# Mic-Breakout_v13.net
KiCad netlist of a schematic drawn in EAGLE
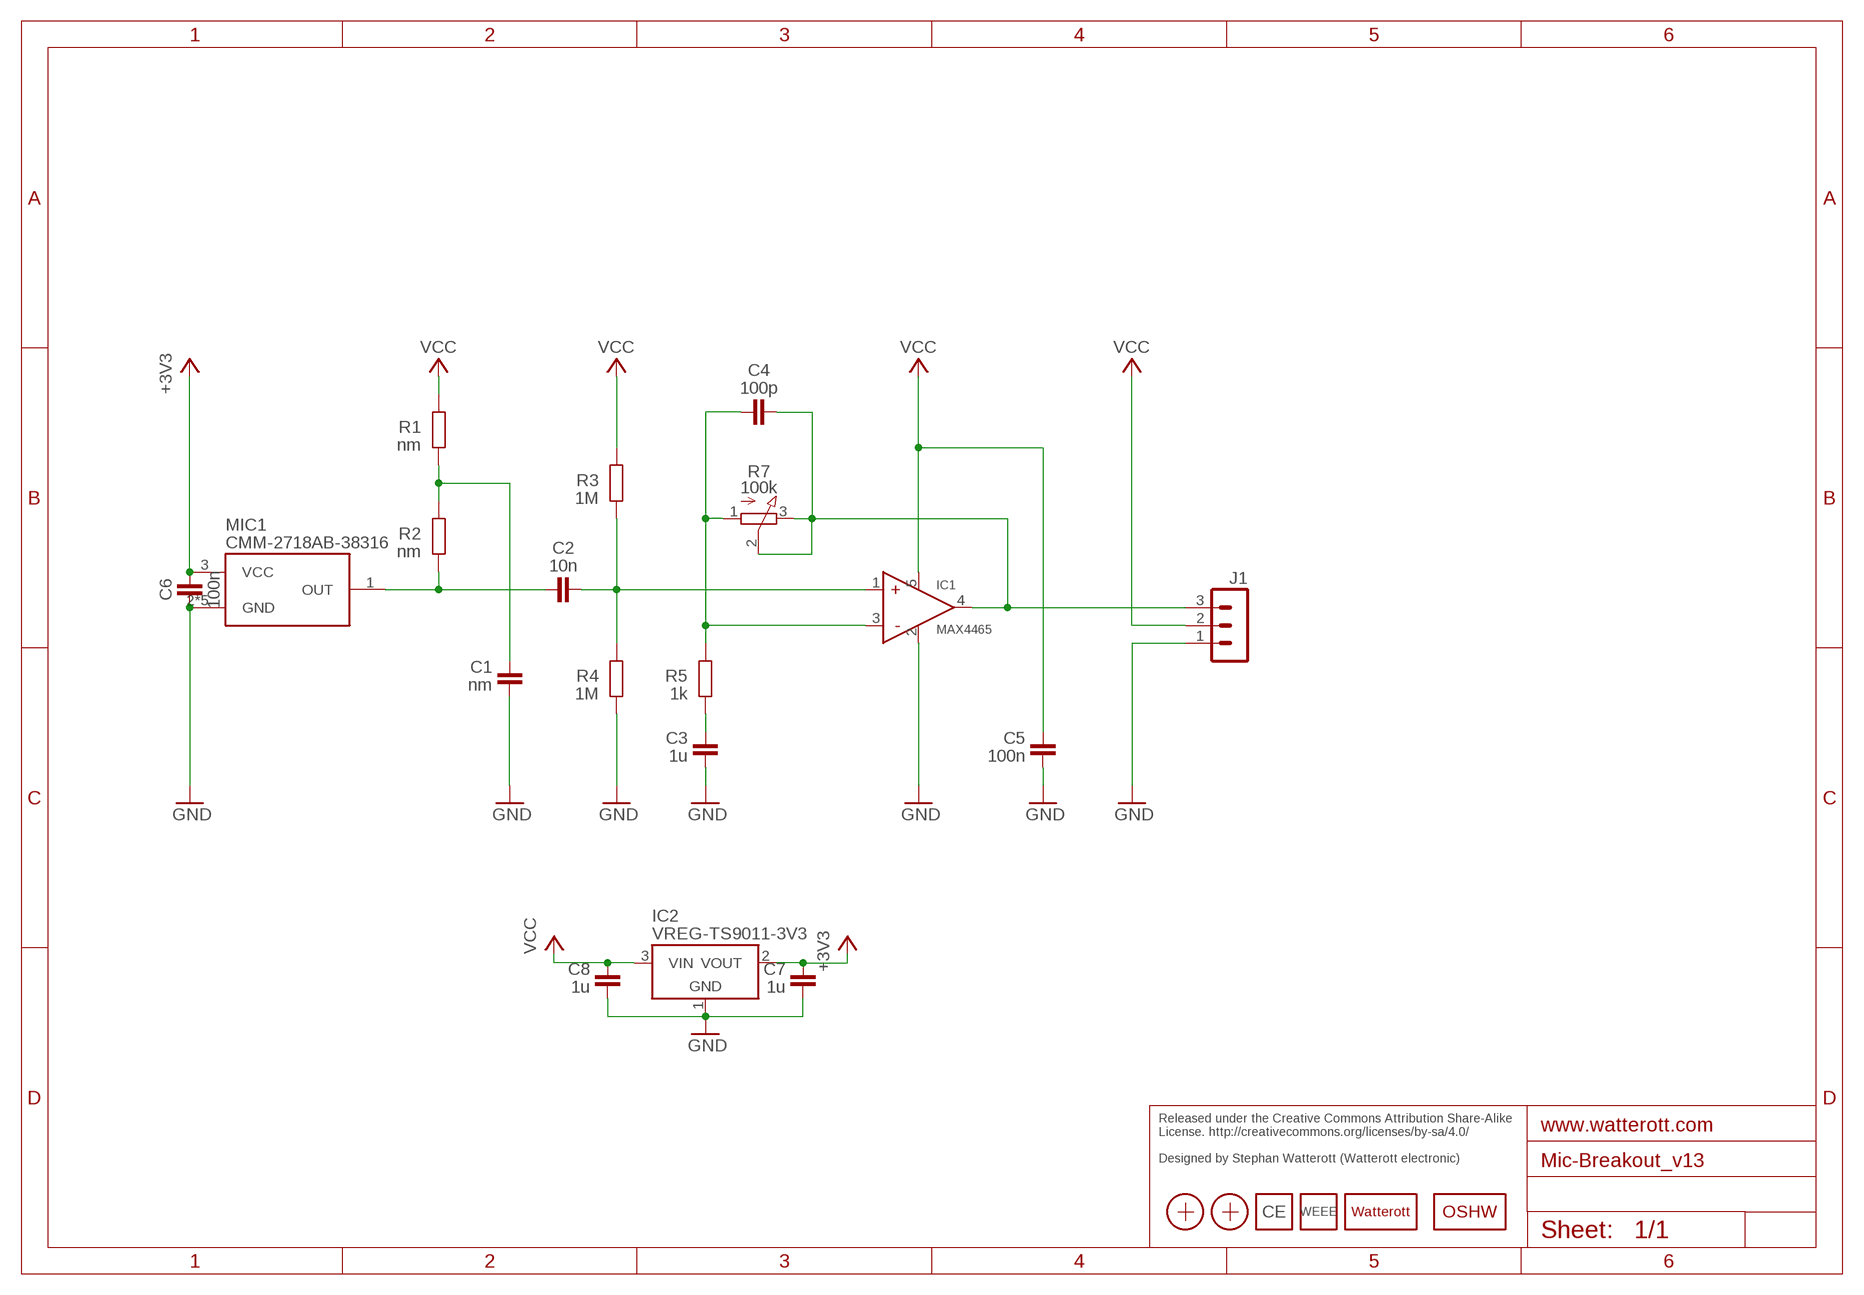
[diagram p0: schematic, sheet 1]

(export (version "E")
  (design (tool "Eeschema 10.0.6"))
  (components
    (comp (ref "C1")
      (value "nm")
      (footprint "eagle-import:C0402")
      (libsource (lib "eagle-import") (part "CAPACITOR-0402"))
    )
    (comp (ref "C2")
      (value "10n")
      (footprint "eagle-import:C0402")
      (libsource (lib "eagle-import") (part "CAPACITOR-0402"))
    )
    (comp (ref "C3")
      (value "1u")
      (footprint "eagle-import:C0402")
      (libsource (lib "eagle-import") (part "CAPACITOR-0402"))
    )
    (comp (ref "C4")
      (value "100p")
      (footprint "eagle-import:C0402")
      (libsource (lib "eagle-import") (part "CAPACITOR-0402"))
    )
    (comp (ref "C5")
      (value "100n")
      (footprint "eagle-import:C0402")
      (libsource (lib "eagle-import") (part "CAPACITOR-0402"))
    )
    (comp (ref "C6")
      (value "100n")
      (footprint "eagle-import:C0402")
      (libsource (lib "eagle-import") (part "CAPACITOR-0402"))
    )
    (comp (ref "C7")
      (value "1u")
      (footprint "eagle-import:C0402")
      (libsource (lib "eagle-import") (part "CAPACITOR-0402"))
    )
    (comp (ref "C8")
      (value "1u")
      (footprint "eagle-import:C0402")
      (libsource (lib "eagle-import") (part "CAPACITOR-0402"))
    )
    (comp (ref "IC1")
      (value "MAX4465")
      (footprint "eagle-import:SOT353")
      (libsource (lib "eagle-import") (part "MAX4465"))
    )
    (comp (ref "IC2")
      (value "VREG-TS9011-3V3")
      (footprint "eagle-import:SOT23")
      (libsource (lib "eagle-import") (part "VREG-TS9011-3V3"))
    )
    (comp (ref "J1")
      (value "MA03-1")
      (footprint "eagle-import:MA03-1")
      (libsource (lib "eagle-import") (part "MA03-1"))
    )
    (comp (ref "LOGO1")
      (value "LOGO-S_PLACE_M")
      (footprint "eagle-import:SPARK_TPLACE_M")
      (libsource (lib "eagle-import") (part "LOGO-S_PLACE_M"))
    )
    (comp (ref "LOGO2")
      (value "OSHW_LOGOX0100")
      (footprint "eagle-import:OSHW_6X100")
      (libsource (lib "eagle-import") (part "OSHW_LOGOX0100"))
    )
    (comp (ref "LOGO3")
      (value "LOGO_WEEE-4")
      (footprint "eagle-import:WEEE_4MM")
      (libsource (lib "eagle-import") (part "LOGO_WEEE-4"))
    )
    (comp (ref "LOGO4")
      (value "LOGO_CE-2")
      (footprint "eagle-import:CE_2MM")
      (libsource (lib "eagle-import") (part "LOGO_CE-2"))
    )
    (comp (ref "MIC1")
      (value "CMM-2718AB-38316")
      (footprint "eagle-import:CMM-2718AB-38316")
      (libsource (lib "eagle-import") (part "CMM-2718AB-38316CMM-2718AB-38316"))
    )
    (comp (ref "R1")
      (value "nm")
      (footprint "eagle-import:C0402")
      (libsource (lib "eagle-import") (part "RESISTOR-0402"))
    )
    (comp (ref "R2")
      (value "nm")
      (footprint "eagle-import:C0402")
      (libsource (lib "eagle-import") (part "RESISTOR-0402"))
    )
    (comp (ref "R3")
      (value "1M")
      (footprint "eagle-import:C0402")
      (libsource (lib "eagle-import") (part "RESISTOR-0402"))
    )
    (comp (ref "R4")
      (value "1M")
      (footprint "eagle-import:C0402")
      (libsource (lib "eagle-import") (part "RESISTOR-0402"))
    )
    (comp (ref "R5")
      (value "1k")
      (footprint "eagle-import:C0402")
      (libsource (lib "eagle-import") (part "RESISTOR-0402"))
    )
    (comp (ref "R7")
      (value "100k")
      (footprint "eagle-import:POT_EVM3Y")
      (libsource (lib "eagle-import") (part "POTEVM3Y"))
    )
    (comp (ref "X1")
      (value "PASSER-04")
      (footprint "eagle-import:PASSER_04MM")
      (libsource (lib "eagle-import") (part "PASSER-04"))
    )
    (comp (ref "X2")
      (value "PASSER-04")
      (footprint "eagle-import:PASSER_04MM")
      (libsource (lib "eagle-import") (part "PASSER-04"))
    )
  )
  (nets
    (net (code "1") (name "+3V3") (class "Default")
      (node (ref "C6") (pin "2") (pinfunction "2_2") (pintype "passive"))
      (node (ref "C7") (pin "2") (pinfunction "2_2") (pintype "passive"))
      (node (ref "IC2") (pin "2") (pinfunction "VOUT_2") (pintype "power_in"))
      (node (ref "MIC1") (pin "3") (pinfunction "VCC_3") (pintype "bidirectional"))
    )
    (net (code "2") (name "GND") (class "Default")
      (node (ref "C1") (pin "1") (pinfunction "1_1") (pintype "passive"))
      (node (ref "C3") (pin "1") (pinfunction "1_1") (pintype "passive"))
      (node (ref "C5") (pin "1") (pinfunction "1_1") (pintype "passive"))
      (node (ref "C6") (pin "1") (pinfunction "1_1") (pintype "passive"))
      (node (ref "C7") (pin "1") (pinfunction "1_1") (pintype "passive"))
      (node (ref "C8") (pin "1") (pinfunction "1_1") (pintype "passive"))
      (node (ref "IC1") (pin "2") (pinfunction "GND_2") (pintype "power_in"))
      (node (ref "IC2") (pin "1") (pinfunction "GND_1") (pintype "power_in"))
      (node (ref "J1") (pin "1") (pinfunction "1_1") (pintype "passive"))
      (node (ref "MIC1") (pin "2") (pinfunction "GND_2") (pintype "bidirectional"))
      (node (ref "MIC1") (pin "4") (pinfunction "GND_4") (pintype "bidirectional"))
      (node (ref "MIC1") (pin "5") (pinfunction "GND_5") (pintype "bidirectional"))
      (node (ref "MIC1") (pin "6") (pinfunction "GND_6") (pintype "bidirectional"))
      (node (ref "MIC1") (pin "7") (pinfunction "GND_7") (pintype "bidirectional"))
      (node (ref "R4") (pin "1") (pinfunction "1_1") (pintype "passive"))
    )
    (net (code "3") (name "Net-(C1-Pad2)") (class "Default")
      (node (ref "C1") (pin "2") (pinfunction "2_2") (pintype "passive"))
      (node (ref "R1") (pin "1") (pinfunction "1_1") (pintype "passive"))
      (node (ref "R2") (pin "2") (pinfunction "2_2") (pintype "passive"))
    )
    (net (code "4") (name "Net-(C3-Pad2)") (class "Default")
      (node (ref "C3") (pin "2") (pinfunction "2_2") (pintype "passive"))
      (node (ref "R5") (pin "1") (pinfunction "1_1") (pintype "passive"))
    )
    (net (code "5") (name "Net-(IC1-+)") (class "Default")
      (node (ref "C2") (pin "2") (pinfunction "2_2") (pintype "passive"))
      (node (ref "IC1") (pin "1") (pinfunction "+_1") (pintype "input"))
      (node (ref "R3") (pin "1") (pinfunction "1_1") (pintype "passive"))
      (node (ref "R4") (pin "2") (pinfunction "2_2") (pintype "passive"))
    )
    (net (code "6") (name "Net-(IC1--)") (class "Default")
      (node (ref "C4") (pin "2") (pinfunction "2_2") (pintype "passive"))
      (node (ref "IC1") (pin "3") (pinfunction "-_3") (pintype "input"))
      (node (ref "R5") (pin "2") (pinfunction "2_2") (pintype "passive"))
      (node (ref "R7") (pin "1") (pinfunction "A_1") (pintype "passive"))
    )
    (net (code "7") (name "Net-(IC1-OUT)") (class "Default")
      (node (ref "C4") (pin "1") (pinfunction "1_1") (pintype "passive"))
      (node (ref "IC1") (pin "4") (pinfunction "OUT_4") (pintype "output"))
      (node (ref "J1") (pin "3") (pinfunction "3_3") (pintype "passive"))
      (node (ref "R7") (pin "2") (pinfunction "S_2") (pintype "passive"))
      (node (ref "R7") (pin "3") (pinfunction "E_3") (pintype "passive"))
    )
    (net (code "8") (name "Net-(MIC1-OUT)") (class "Default")
      (node (ref "C2") (pin "1") (pinfunction "1_1") (pintype "passive"))
      (node (ref "MIC1") (pin "1") (pinfunction "OUT_1") (pintype "bidirectional"))
      (node (ref "R2") (pin "1") (pinfunction "1_1") (pintype "passive"))
    )
    (net (code "9") (name "VCC") (class "Default")
      (node (ref "C5") (pin "2") (pinfunction "2_2") (pintype "passive"))
      (node (ref "C8") (pin "2") (pinfunction "2_2") (pintype "passive"))
      (node (ref "IC1") (pin "5") (pinfunction "VCC_5") (pintype "power_in"))
      (node (ref "IC2") (pin "3") (pinfunction "VIN_3") (pintype "power_in"))
      (node (ref "J1") (pin "2") (pinfunction "2_2") (pintype "passive"))
      (node (ref "R1") (pin "2") (pinfunction "2_2") (pintype "passive"))
      (node (ref "R3") (pin "2") (pinfunction "2_2") (pintype "passive"))
    )
  )
)
